# XBee3.net
KiCad netlist of a schematic drawn in EAGLE
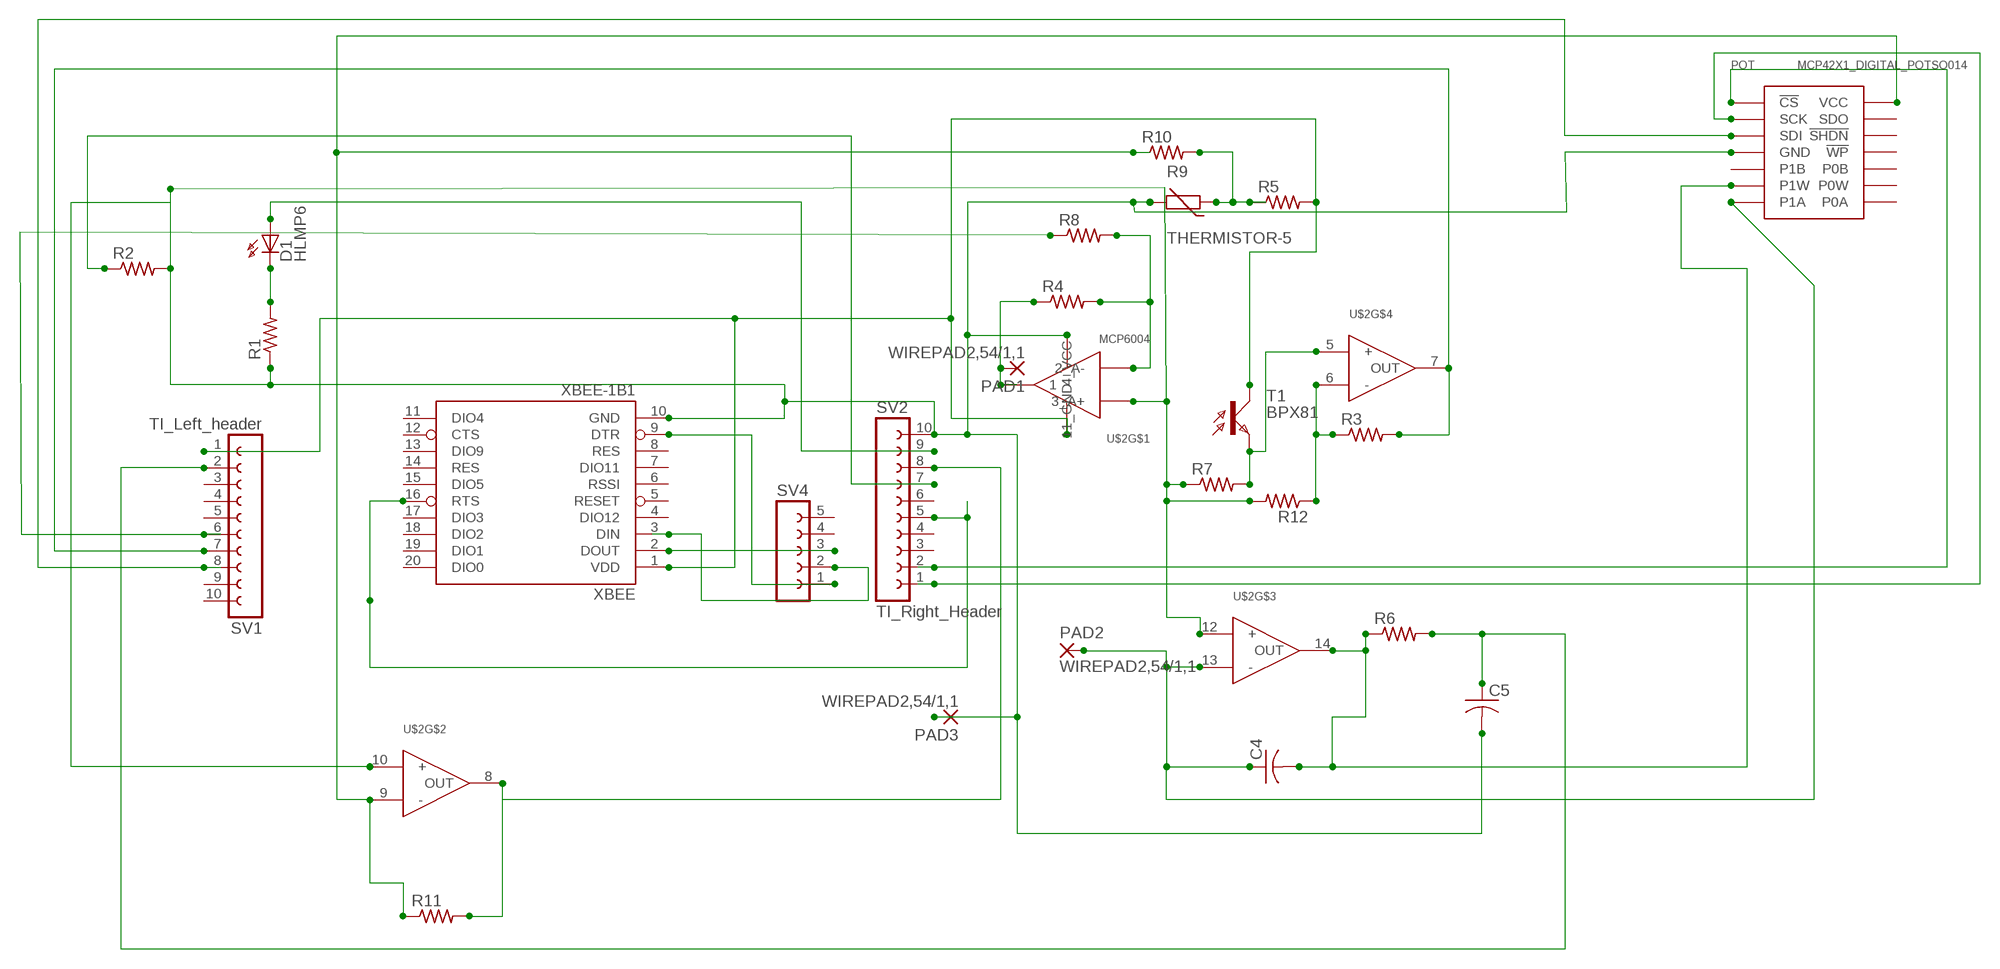
[diagram p0: schematic, sheet 1]

(export (version "E")
  (design (tool "Eeschema 10.0.6"))
  (components
    (comp (ref "C4")
      (value "C-USC0603")
      (footprint "eagle-import:C0603")
      (libsource (lib "eagle-import") (part "C-USC0603"))
    )
    (comp (ref "C5")
      (value "C-USC0603")
      (footprint "eagle-import:C0603")
      (libsource (lib "eagle-import") (part "C-USC0603"))
    )
    (comp (ref "D1")
      (value "HLMP6")
      (footprint "eagle-import:HLMP6")
      (fields (field (name "MF") "AGILENT TECHNOLOGIES") (field (name "MPN") "HLMP-6500"))
      (libsource (lib "eagle-import") (part "HLMP6"))
    )
    (comp (ref "PAD1")
      (value "WIREPAD2,54/1,1")
      (footprint "eagle-import:2,54_1,1")
      (libsource (lib "eagle-import") (part "WIREPAD2,54/1,1"))
    )
    (comp (ref "PAD2")
      (value "WIREPAD2,54/1,1")
      (footprint "eagle-import:2,54_1,1")
      (libsource (lib "eagle-import") (part "WIREPAD2,54/1,1"))
    )
    (comp (ref "PAD3")
      (value "WIREPAD2,54/1,1")
      (footprint "eagle-import:2,54_1,1")
      (libsource (lib "eagle-import") (part "WIREPAD2,54/1,1"))
    )
    (comp (ref "POT")
      (value "MCP42X1_DIGITAL_POTSO014")
      (footprint "eagle-import:SO014")
      (libsource (lib "eagle-import") (part "MCP42X1_DIGITAL_POTSO014"))
    )
    (comp (ref "R1")
      (value "R-US_R0603")
      (footprint "eagle-import:R0603")
      (libsource (lib "eagle-import") (part "R-US_R0603"))
    )
    (comp (ref "R2")
      (value "R-US_R0603")
      (footprint "eagle-import:R0603")
      (libsource (lib "eagle-import") (part "R-US_R0603"))
    )
    (comp (ref "R3")
      (value "R-US_R0603")
      (footprint "eagle-import:R0603")
      (libsource (lib "eagle-import") (part "R-US_R0603"))
    )
    (comp (ref "R4")
      (value "R-US_R0603")
      (footprint "eagle-import:R0603")
      (libsource (lib "eagle-import") (part "R-US_R0603"))
    )
    (comp (ref "R5")
      (value "R-US_R0603")
      (footprint "eagle-import:R0603")
      (libsource (lib "eagle-import") (part "R-US_R0603"))
    )
    (comp (ref "R6")
      (value "R-US_R0603")
      (footprint "eagle-import:R0603")
      (libsource (lib "eagle-import") (part "R-US_R0603"))
    )
    (comp (ref "R7")
      (value "R-US_R0603")
      (footprint "eagle-import:R0603")
      (libsource (lib "eagle-import") (part "R-US_R0603"))
    )
    (comp (ref "R8")
      (value "R-US_R0603")
      (footprint "eagle-import:R0603")
      (libsource (lib "eagle-import") (part "R-US_R0603"))
    )
    (comp (ref "R9")
      (value "THERMISTOR-5")
      (footprint "eagle-import:R-5")
      (libsource (lib "eagle-import") (part "THERMISTOR-5"))
    )
    (comp (ref "R10")
      (value "R-US_R0603")
      (footprint "eagle-import:R0603")
      (libsource (lib "eagle-import") (part "R-US_R0603"))
    )
    (comp (ref "R11")
      (value "R-US_R0603")
      (footprint "eagle-import:R0603")
      (libsource (lib "eagle-import") (part "R-US_R0603"))
    )
    (comp (ref "R12")
      (value "R-US_R0603")
      (footprint "eagle-import:R0603")
      (libsource (lib "eagle-import") (part "R-US_R0603"))
    )
    (comp (ref "SV1")
      (value "TI_Left_header")
      (footprint "eagle-import:FE10")
      (libsource (lib "eagle-import") (part "FE10-1"))
    )
    (comp (ref "SV2")
      (value "TI_Right_Header")
      (footprint "eagle-import:FE10")
      (libsource (lib "eagle-import") (part "FE10-1"))
    )
    (comp (ref "SV4")
      (value "FE05-1")
      (footprint "eagle-import:FE05-1")
      (libsource (lib "eagle-import") (part "FE05-1"))
    )
    (comp (ref "T1")
      (value "BPX81")
      (footprint "eagle-import:BPX81")
      (libsource (lib "eagle-import") (part "BPX81"))
    )
    (comp (ref "U$2")
      (value "MCP6004")
      (footprint "eagle-import:SO014")
      (libsource (lib "eagle-import") (part "MCP6004"))
    )
    (comp (ref "XBEE")
      (value "XBEE-1B1")
      (footprint "eagle-import:XBEE-1")
      (libsource (lib "eagle-import") (part "XBEE-1B1"))
    )
  )
  (nets
    (net (code "1") (name "Net-(C5-Pad1)") (class "Default")
      (node (ref "C5") (pin "1") (pinfunction "1_1") (pintype "passive"))
      (node (ref "R6") (pin "2") (pinfunction "2_2") (pintype "passive"))
      (node (ref "SV1") (pin "2") (pinfunction "2_2") (pintype "passive"))
    )
    (net (code "2") (name "Net-(D1-PadA)") (class "Default")
      (node (ref "D1") (pin "A") (pinfunction "A_A") (pintype "passive"))
      (node (ref "SV2") (pin "9") (pinfunction "9_9") (pintype "passive"))
    )
    (net (code "3") (name "Net-(D1-PadK)") (class "Default")
      (node (ref "D1") (pin "K") (pinfunction "K_K") (pintype "passive"))
      (node (ref "R1") (pin "2") (pinfunction "2_2") (pintype "passive"))
    )
    (net (code "4") (name "Net-(PAD1-P)") (class "Default")
      (node (ref "PAD1") (pin "1") (pinfunction "P_1") (pintype "passive"))
      (node (ref "R4") (pin "1") (pinfunction "1_1") (pintype "passive"))
      (node (ref "U$2") (pin "1") (pinfunction "1_1") (pintype "bidirectional"))
    )
    (net (code "5") (name "Net-(PAD2-P)") (class "Default")
      (node (ref "C4") (pin "1") (pinfunction "1_1") (pintype "passive"))
      (node (ref "PAD2") (pin "1") (pinfunction "P_1") (pintype "passive"))
      (node (ref "POT") (pin "P7") (pinfunction "P1A_P7") (pintype "bidirectional"))
      (node (ref "U$2") (pin "13") (pinfunction "-_13") (pintype "bidirectional"))
    )
    (net (code "6") (name "Net-(PAD3-P)") (class "Default")
      (node (ref "C5") (pin "2") (pinfunction "2_2") (pintype "passive"))
      (node (ref "PAD3") (pin "1") (pinfunction "P_1") (pintype "passive"))
      (node (ref "POT") (pin "P4") (pinfunction "GND_P4") (pintype "bidirectional"))
      (node (ref "R1") (pin "1") (pinfunction "1_1") (pintype "passive"))
      (node (ref "R12") (pin "2") (pinfunction "2_2") (pintype "passive"))
      (node (ref "R2") (pin "2") (pinfunction "2_2") (pintype "passive"))
      (node (ref "R7") (pin "1") (pinfunction "1_1") (pintype "passive"))
      (node (ref "R9") (pin "2") (pinfunction "2_2") (pintype "passive"))
      (node (ref "SV2") (pin "10") (pinfunction "10_10") (pintype "passive"))
      (node (ref "U$2") (pin "10") (pinfunction "+_10") (pintype "bidirectional"))
      (node (ref "U$2") (pin "11") (pinfunction "11_GND_11") (pintype "power_in"))
      (node (ref "U$2") (pin "12") (pinfunction "+_12") (pintype "bidirectional"))
      (node (ref "U$2") (pin "3") (pinfunction "3_A+_3") (pintype "bidirectional"))
      (node (ref "XBEE") (pin "10") (pinfunction "GND_10") (pintype "power_in"))
    )
    (net (code "7") (name "Net-(POT-P1W)") (class "Default")
      (node (ref "C4") (pin "2") (pinfunction "2_2") (pintype "passive"))
      (node (ref "POT") (pin "P6") (pinfunction "P1W_P6") (pintype "bidirectional"))
      (node (ref "R6") (pin "1") (pinfunction "1_1") (pintype "passive"))
      (node (ref "U$2") (pin "14") (pinfunction "OUT_14") (pintype "bidirectional"))
    )
    (net (code "8") (name "Net-(POT-SCK)") (class "Default")
      (node (ref "POT") (pin "P2") (pinfunction "SCK_P2") (pintype "bidirectional"))
      (node (ref "SV2") (pin "1") (pinfunction "1_1") (pintype "passive"))
    )
    (net (code "9") (name "Net-(POT-SDI)") (class "Default")
      (node (ref "POT") (pin "P3") (pinfunction "SDI_P3") (pintype "bidirectional"))
      (node (ref "SV1") (pin "8") (pinfunction "8_8") (pintype "passive"))
    )
    (net (code "10") (name "Net-(POT-VCC)") (class "Default")
      (node (ref "POT") (pin "P14") (pinfunction "VCC_P14") (pintype "bidirectional"))
      (node (ref "R10") (pin "1") (pinfunction "1_1") (pintype "passive"))
      (node (ref "R11") (pin "1") (pinfunction "1_1") (pintype "passive"))
      (node (ref "U$2") (pin "9") (pinfunction "-_9") (pintype "bidirectional"))
    )
    (net (code "11") (name "Net-(POT-~{CS})") (class "Default")
      (node (ref "POT") (pin "P1") (pinfunction "~{CS}_P1") (pintype "bidirectional"))
      (node (ref "SV2") (pin "2") (pinfunction "2_2") (pintype "passive"))
    )
    (net (code "12") (name "Net-(R2-Pad1)") (class "Default")
      (node (ref "R2") (pin "1") (pinfunction "1_1") (pintype "passive"))
      (node (ref "SV2") (pin "7") (pinfunction "7_7") (pintype "passive"))
    )
    (net (code "13") (name "Net-(R8-Pad1)") (class "Default")
      (node (ref "R8") (pin "1") (pinfunction "1_1") (pintype "passive"))
      (node (ref "SV1") (pin "6") (pinfunction "6_6") (pintype "passive"))
    )
    (net (code "14") (name "Net-(R10-Pad2)") (class "Default")
      (node (ref "R10") (pin "2") (pinfunction "2_2") (pintype "passive"))
      (node (ref "R5") (pin "1") (pinfunction "1_1") (pintype "passive"))
      (node (ref "R9") (pin "1") (pinfunction "1_1") (pintype "passive"))
    )
    (net (code "15") (name "Net-(U$2A-2_A-)") (class "Default")
      (node (ref "R4") (pin "2") (pinfunction "2_2") (pintype "passive"))
      (node (ref "R8") (pin "2") (pinfunction "2_2") (pintype "passive"))
      (node (ref "U$2") (pin "2") (pinfunction "2_A-_2") (pintype "bidirectional"))
    )
    (net (code "16") (name "Net-(U$2A-4_VCC)") (class "Default")
      (node (ref "R5") (pin "2") (pinfunction "2_2") (pintype "passive"))
      (node (ref "SV1") (pin "1") (pinfunction "1_1") (pintype "passive"))
      (node (ref "T1") (pin "C") (pinfunction "C_C") (pintype "passive"))
      (node (ref "U$2") (pin "4") (pinfunction "4_VCC_4") (pintype "power_in"))
      (node (ref "XBEE") (pin "1") (pinfunction "VDD_1") (pintype "power_in"))
    )
    (net (code "17") (name "Net-(U$2B-OUT)") (class "Default")
      (node (ref "R11") (pin "2") (pinfunction "2_2") (pintype "passive"))
      (node (ref "SV2") (pin "8") (pinfunction "8_8") (pintype "passive"))
      (node (ref "U$2") (pin "8") (pinfunction "OUT_8") (pintype "bidirectional"))
    )
    (net (code "18") (name "Net-(U$2D-+)") (class "Default")
      (node (ref "R7") (pin "2") (pinfunction "2_2") (pintype "passive"))
      (node (ref "T1") (pin "E") (pinfunction "E_E") (pintype "passive"))
      (node (ref "U$2") (pin "5") (pinfunction "+_5") (pintype "bidirectional"))
    )
    (net (code "19") (name "Net-(U$2D--)") (class "Default")
      (node (ref "R12") (pin "1") (pinfunction "1_1") (pintype "passive"))
      (node (ref "R3") (pin "1") (pinfunction "1_1") (pintype "passive"))
      (node (ref "U$2") (pin "6") (pinfunction "-_6") (pintype "bidirectional"))
    )
    (net (code "20") (name "Net-(U$2D-OUT)") (class "Default")
      (node (ref "R3") (pin "2") (pinfunction "2_2") (pintype "passive"))
      (node (ref "SV1") (pin "7") (pinfunction "7_7") (pintype "passive"))
      (node (ref "U$2") (pin "7") (pinfunction "OUT_7") (pintype "bidirectional"))
    )
    (net (code "21") (name "Net-(XBEE-DIN)") (class "Default")
      (node (ref "SV4") (pin "2") (pinfunction "2_2") (pintype "passive"))
      (node (ref "XBEE") (pin "3") (pinfunction "DIN_3") (pintype "input"))
    )
    (net (code "22") (name "Net-(XBEE-DOUT)") (class "Default")
      (node (ref "SV4") (pin "3") (pinfunction "3_3") (pintype "passive"))
      (node (ref "XBEE") (pin "2") (pinfunction "DOUT_2") (pintype "output"))
    )
    (net (code "23") (name "Net-(XBEE-DTR)") (class "Default")
      (node (ref "SV4") (pin "1") (pinfunction "1_1") (pintype "passive"))
      (node (ref "XBEE") (pin "9") (pinfunction "DTR_9") (pintype "bidirectional"))
    )
    (net (code "24") (name "Net-(XBEE-RTS)") (class "Default")
      (node (ref "SV2") (pin "5") (pinfunction "5_5") (pintype "passive"))
      (node (ref "XBEE") (pin "16") (pinfunction "RTS_16") (pintype "input"))
    )
    (net (code "25") (name "unconnected-(POT-P0A-PadP8)") (class "Default")
      (node (ref "POT") (pin "P8") (pinfunction "P0A_P8") (pintype "bidirectional"))
    )
    (net (code "26") (name "unconnected-(POT-P0B-PadP10)") (class "Default")
      (node (ref "POT") (pin "P10") (pinfunction "P0B_P10") (pintype "bidirectional"))
    )
    (net (code "27") (name "unconnected-(POT-P0W-PadP9)") (class "Default")
      (node (ref "POT") (pin "P9") (pinfunction "P0W_P9") (pintype "bidirectional"))
    )
    (net (code "28") (name "unconnected-(POT-P1B-PadP5)") (class "Default")
      (node (ref "POT") (pin "P5") (pinfunction "P1B_P5") (pintype "bidirectional"))
    )
    (net (code "29") (name "unconnected-(POT-SDO-PadP13)") (class "Default")
      (node (ref "POT") (pin "P13") (pinfunction "SDO_P13") (pintype "bidirectional"))
    )
    (net (code "30") (name "unconnected-(POT-~{SHDN}-PadP12)") (class "Default")
      (node (ref "POT") (pin "P12") (pinfunction "~{SHDN}_P12") (pintype "bidirectional"))
    )
    (net (code "31") (name "unconnected-(POT-~{WP}-PadP11)") (class "Default")
      (node (ref "POT") (pin "P11") (pinfunction "~{WP}_P11") (pintype "bidirectional"))
    )
    (net (code "32") (name "unconnected-(SV1-Pad3)") (class "Default")
      (node (ref "SV1") (pin "3") (pinfunction "3_3") (pintype "passive"))
    )
    (net (code "33") (name "unconnected-(SV1-Pad4)") (class "Default")
      (node (ref "SV1") (pin "4") (pinfunction "4_4") (pintype "passive"))
    )
    (net (code "34") (name "unconnected-(SV1-Pad5)") (class "Default")
      (node (ref "SV1") (pin "5") (pinfunction "5_5") (pintype "passive"))
    )
    (net (code "35") (name "unconnected-(SV1-Pad9)") (class "Default")
      (node (ref "SV1") (pin "9") (pinfunction "9_9") (pintype "passive"))
    )
    (net (code "36") (name "unconnected-(SV1-Pad10)") (class "Default")
      (node (ref "SV1") (pin "10") (pinfunction "10_10") (pintype "passive"))
    )
    (net (code "37") (name "unconnected-(SV2-Pad3)") (class "Default")
      (node (ref "SV2") (pin "3") (pinfunction "3_3") (pintype "passive"))
    )
    (net (code "38") (name "unconnected-(SV2-Pad4)") (class "Default")
      (node (ref "SV2") (pin "4") (pinfunction "4_4") (pintype "passive"))
    )
    (net (code "39") (name "unconnected-(SV2-Pad6)") (class "Default")
      (node (ref "SV2") (pin "6") (pinfunction "6_6") (pintype "passive"))
    )
    (net (code "40") (name "unconnected-(SV4-Pad4)") (class "Default")
      (node (ref "SV4") (pin "4") (pinfunction "4_4") (pintype "passive"))
    )
    (net (code "41") (name "unconnected-(SV4-Pad5)") (class "Default")
      (node (ref "SV4") (pin "5") (pinfunction "5_5") (pintype "passive"))
    )
    (net (code "42") (name "unconnected-(XBEE-CTS-Pad12)") (class "Default")
      (node (ref "XBEE") (pin "12") (pinfunction "CTS_12") (pintype "output"))
    )
    (net (code "43") (name "unconnected-(XBEE-DIO0-Pad20)") (class "Default")
      (node (ref "XBEE") (pin "20") (pinfunction "DIO0_20") (pintype "bidirectional"))
    )
    (net (code "44") (name "unconnected-(XBEE-DIO1-Pad19)") (class "Default")
      (node (ref "XBEE") (pin "19") (pinfunction "DIO1_19") (pintype "bidirectional"))
    )
    (net (code "45") (name "unconnected-(XBEE-DIO2-Pad18)") (class "Default")
      (node (ref "XBEE") (pin "18") (pinfunction "DIO2_18") (pintype "bidirectional"))
    )
    (net (code "46") (name "unconnected-(XBEE-DIO3-Pad17)") (class "Default")
      (node (ref "XBEE") (pin "17") (pinfunction "DIO3_17") (pintype "bidirectional"))
    )
    (net (code "47") (name "unconnected-(XBEE-DIO4-Pad11)") (class "Default")
      (node (ref "XBEE") (pin "11") (pinfunction "DIO4_11") (pintype "bidirectional"))
    )
    (net (code "48") (name "unconnected-(XBEE-DIO5-Pad15)") (class "Default")
      (node (ref "XBEE") (pin "15") (pinfunction "DIO5_15") (pintype "bidirectional"))
    )
    (net (code "49") (name "unconnected-(XBEE-DIO9-Pad13)") (class "Default")
      (node (ref "XBEE") (pin "13") (pinfunction "DIO9_13") (pintype "bidirectional"))
    )
    (net (code "50") (name "unconnected-(XBEE-DIO11-Pad7)") (class "Default")
      (node (ref "XBEE") (pin "7") (pinfunction "DIO11_7") (pintype "bidirectional"))
    )
    (net (code "51") (name "unconnected-(XBEE-DIO12-Pad4)") (class "Default")
      (node (ref "XBEE") (pin "4") (pinfunction "DIO12_4") (pintype "bidirectional"))
    )
    (net (code "52") (name "unconnected-(XBEE-RES-Pad8)") (class "Default")
      (node (ref "XBEE") (pin "8") (pinfunction "RES_8") (pintype "bidirectional"))
    )
    (net (code "53") (name "unconnected-(XBEE-RES-Pad14)") (class "Default")
      (node (ref "XBEE") (pin "14") (pinfunction "RES_14") (pintype "bidirectional"))
    )
    (net (code "54") (name "unconnected-(XBEE-RESET-Pad5)") (class "Default")
      (node (ref "XBEE") (pin "5") (pinfunction "RESET_5") (pintype "input"))
    )
    (net (code "55") (name "unconnected-(XBEE-RSSI-Pad6)") (class "Default")
      (node (ref "XBEE") (pin "6") (pinfunction "RSSI_6") (pintype "bidirectional"))
    )
  )
)
